# TeensyROM.net
KiCad netlist of a schematic drawn in EAGLE
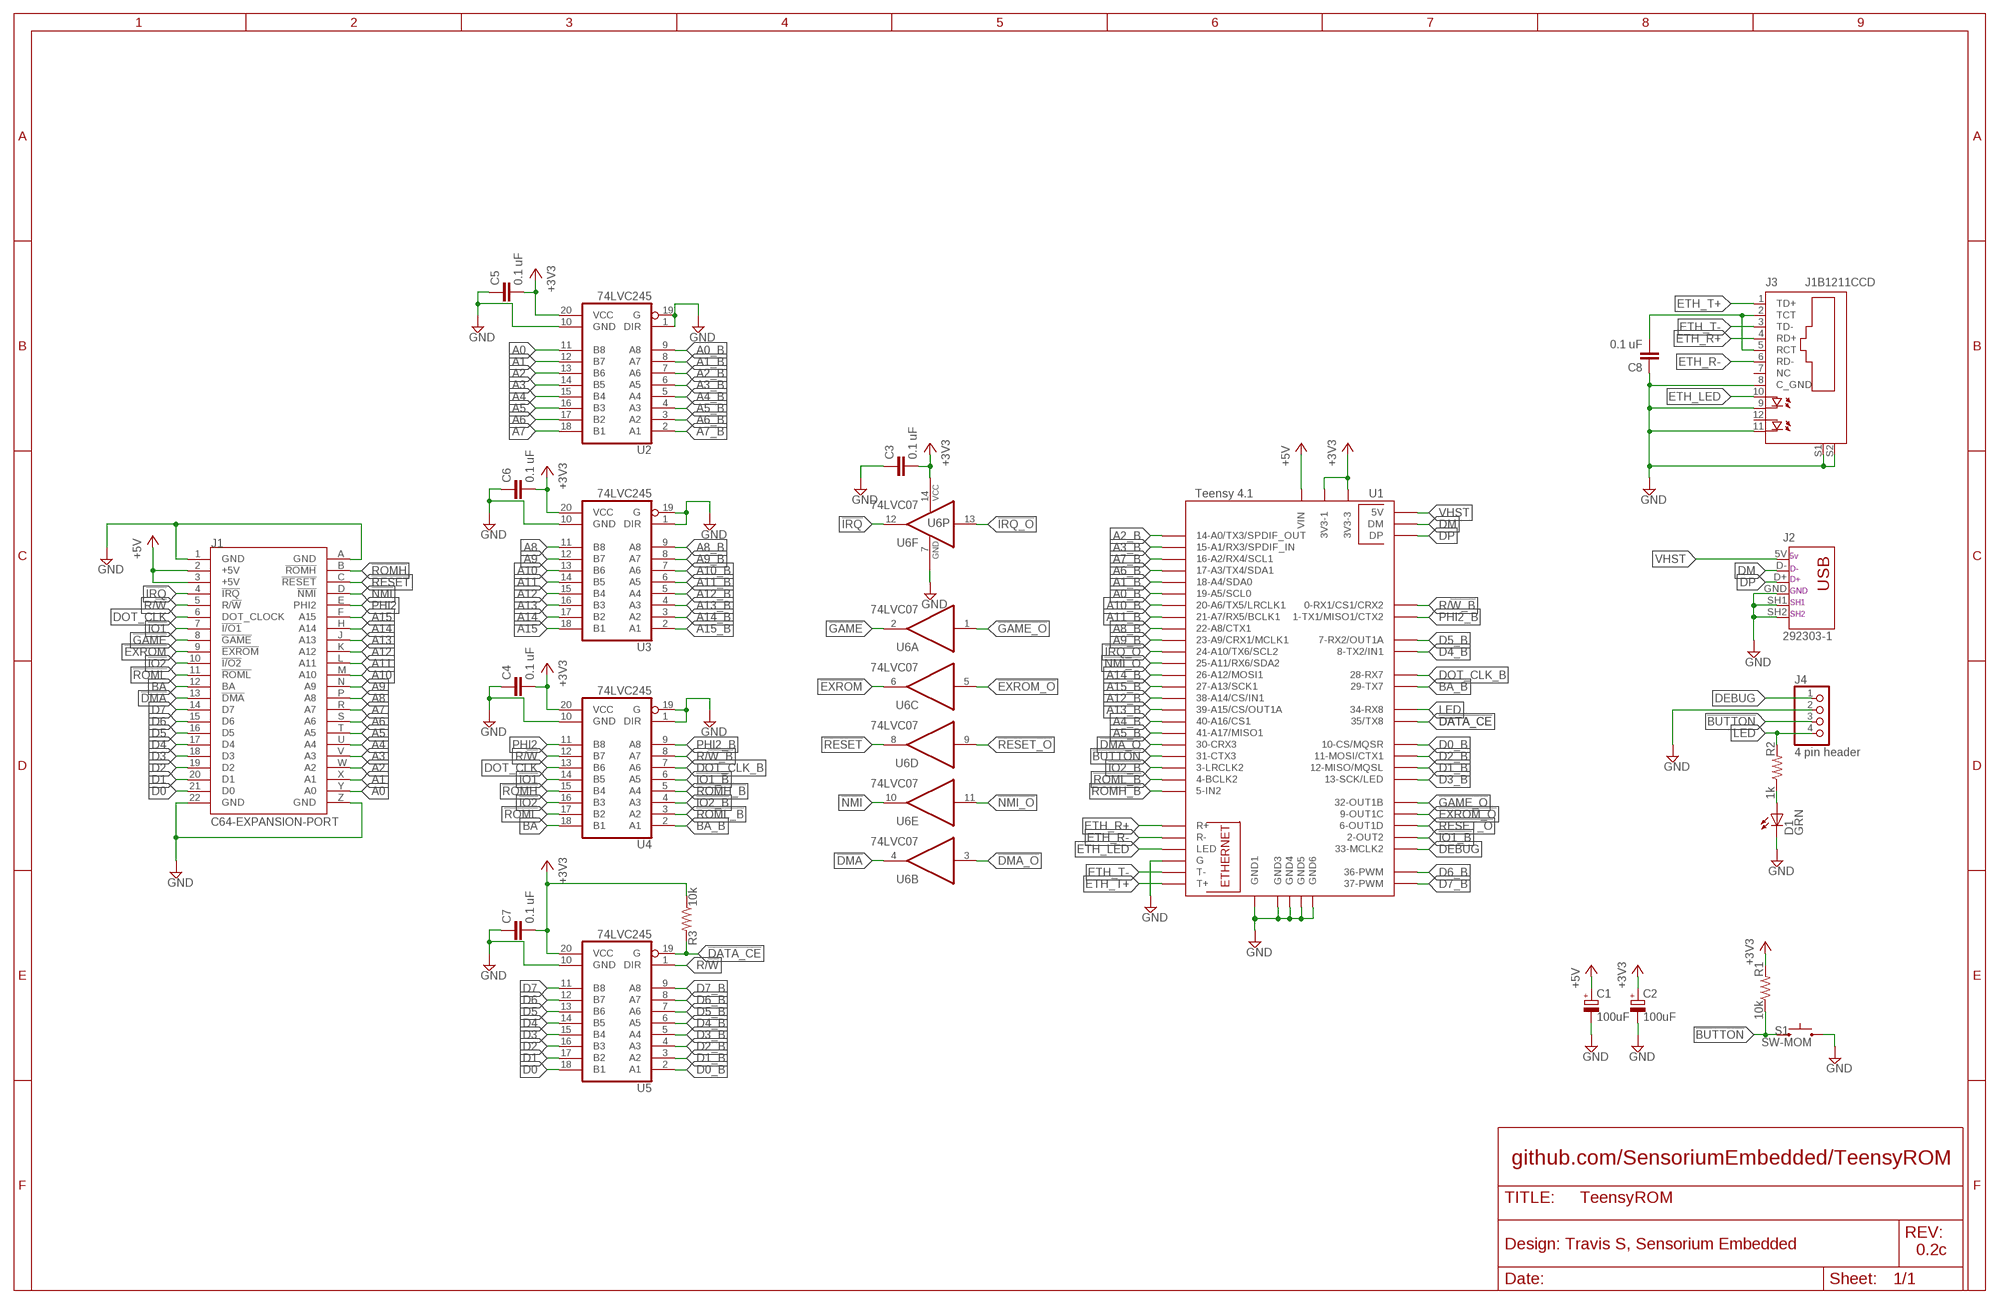
[diagram p0: schematic, sheet 1]

(export (version "E")
  (design (tool "Eeschema 10.0.6"))
  (components
    (comp (ref "C1")
      (value "100uF")
      (footprint "eagle-import:E2-4")
      (libsource (lib "eagle-import") (part "CPOL-EUE2-4"))
    )
    (comp (ref "C2")
      (value "100uF")
      (footprint "eagle-import:E2-4")
      (libsource (lib "eagle-import") (part "CPOL-EUE2-4"))
    )
    (comp (ref "C3")
      (value "0.1 uF")
      (footprint "eagle-import:0805")
      (libsource (lib "eagle-import") (part "CAP-0805-0.1UF-50V"))
    )
    (comp (ref "C4")
      (value "0.1 uF")
      (footprint "eagle-import:0805")
      (libsource (lib "eagle-import") (part "CAP-0805-0.1UF-50V"))
    )
    (comp (ref "C5")
      (value "0.1 uF")
      (footprint "eagle-import:0805")
      (libsource (lib "eagle-import") (part "CAP-0805-0.1UF-50V"))
    )
    (comp (ref "C6")
      (value "0.1 uF")
      (footprint "eagle-import:0805")
      (libsource (lib "eagle-import") (part "CAP-0805-0.1UF-50V"))
    )
    (comp (ref "C7")
      (value "0.1 uF")
      (footprint "eagle-import:0805")
      (libsource (lib "eagle-import") (part "CAP-0805-0.1UF-50V"))
    )
    (comp (ref "C8")
      (value "0.1 uF")
      (footprint "eagle-import:0805")
      (libsource (lib "eagle-import") (part "CAP-0805-0.1UF-50V"))
    )
    (comp (ref "D1")
      (value "GRN")
      (footprint "eagle-import:LED-3MM-PTH")
      (libsource (lib "eagle-import") (part "LED-3MM-GRN"))
    )
    (comp (ref "J1")
      (value "C64-EXPANSION-PORT")
      (footprint "eagle-import:EXPANSIO_SQ")
      (libsource (lib "eagle-import") (part "C64-EXPANSIONPNARROW"))
    )
    (comp (ref "J2")
      (value "292303-1")
      (footprint "eagle-import:USB")
      (libsource (lib "eagle-import") (part "USB-787616"))
    )
    (comp (ref "J3")
      (value "J1B1211CCD")
      (footprint "eagle-import:CONN12_J1B1211CCD_WIZ")
      (fields (field (name "COPYRIGHT") "Copyright (C) 2023 Ultra Librarian. All rights reserved."))
      (libsource (lib "eagle-import") (part "J1B1211CCD"))
    )
    (comp (ref "J4")
      (value "4 pin header")
      (footprint "eagle-import:1X04")
      (libsource (lib "eagle-import") (part "PINHD-1X4"))
    )
    (comp (ref "R1")
      (value "10k")
      (footprint "eagle-import:R0805")
      (libsource (lib "eagle-import") (part "R-US_R0805"))
    )
    (comp (ref "R2")
      (value "1k")
      (footprint "eagle-import:R0805")
      (libsource (lib "eagle-import") (part "R-US_R0805"))
    )
    (comp (ref "R3")
      (value "10k")
      (footprint "eagle-import:R0805")
      (libsource (lib "eagle-import") (part "R-US_R0805"))
    )
    (comp (ref "S1")
      (value "SW-MOM")
      (footprint "eagle-import:TACTILE-PTH")
      (libsource (lib "eagle-import") (part "SWITCH-MOMENTARY-2PTH"))
    )
    (comp (ref "U1")
      (value "Teensy 4.1")
      (footprint "eagle-import:TEENSY41")
      (libsource (lib "eagle-import") (part "TEENSY41"))
    )
    (comp (ref "U2")
      (value "74LVC245")
      (footprint "eagle-import:SO20W")
      (libsource (lib "eagle-import") (part "74245DWLS"))
    )
    (comp (ref "U3")
      (value "74LVC245")
      (footprint "eagle-import:SO20W")
      (libsource (lib "eagle-import") (part "74245DWLS"))
    )
    (comp (ref "U4")
      (value "74LVC245")
      (footprint "eagle-import:SO20W")
      (libsource (lib "eagle-import") (part "74245DWLS"))
    )
    (comp (ref "U5")
      (value "74LVC245")
      (footprint "eagle-import:SO20W")
      (libsource (lib "eagle-import") (part "74245DWLS"))
    )
    (comp (ref "U6")
      (value "74LVC07")
      (footprint "eagle-import:SO14")
      (libsource (lib "eagle-import") (part "7407DLS"))
    )
  )
  (nets
    (net (code "1") (name "+3V3") (class "Default")
      (node (ref "C2") (pin "+") (pinfunction "+_+") (pintype "passive"))
      (node (ref "C3") (pin "2") (pinfunction "2_2") (pintype "passive"))
      (node (ref "C4") (pin "2") (pinfunction "2_2") (pintype "passive"))
      (node (ref "C5") (pin "2") (pinfunction "2_2") (pintype "passive"))
      (node (ref "C6") (pin "2") (pinfunction "2_2") (pintype "passive"))
      (node (ref "C7") (pin "2") (pinfunction "2_2") (pintype "passive"))
      (node (ref "R1") (pin "2") (pinfunction "2_2") (pintype "passive"))
      (node (ref "R3") (pin "1") (pinfunction "1_1") (pintype "passive"))
      (node (ref "U1") (pin "3V3-1") (pinfunction "3V3-1_3V3-1") (pintype "bidirectional"))
      (node (ref "U1") (pin "3V3-3") (pinfunction "3V3-3_3V3-3") (pintype "bidirectional"))
      (node (ref "U2") (pin "20") (pinfunction "VCC_20") (pintype "bidirectional"))
      (node (ref "U3") (pin "20") (pinfunction "VCC_20") (pintype "bidirectional"))
      (node (ref "U4") (pin "20") (pinfunction "VCC_20") (pintype "bidirectional"))
      (node (ref "U5") (pin "20") (pinfunction "VCC_20") (pintype "bidirectional"))
      (node (ref "U6") (pin "14") (pinfunction "VCC_14") (pintype "bidirectional"))
    )
    (net (code "2") (name "+5V") (class "Default")
      (node (ref "C1") (pin "+") (pinfunction "+_+") (pintype "passive"))
      (node (ref "J1") (pin "2") (pinfunction "+5V_2") (pintype "power_in"))
      (node (ref "J1") (pin "3") (pinfunction "+5V_3") (pintype "power_in"))
      (node (ref "U1") (pin "VIN") (pinfunction "VIN_VIN") (pintype "bidirectional"))
    )
    (net (code "3") (name "/R{slash}~{W_B}") (class "Default")
      (node (ref "U1") (pin "0-RX1/CS1/CRX2") (pinfunction "0-RX1/CS1/CRX2_0-RX1/CS1/CRX2") (pintype "bidirectional"))
      (node (ref "U4") (pin "8") (pinfunction "A7_8") (pintype "bidirectional"))
    )
    (net (code "4") (name "/R{slash}~{W}") (class "Default")
      (node (ref "J1") (pin "5") (pinfunction "R/~{W}_5") (pintype "output"))
      (node (ref "U4") (pin "12") (pinfunction "B7_12") (pintype "bidirectional"))
      (node (ref "U5") (pin "1") (pinfunction "DIR_1") (pintype "input"))
    )
    (net (code "5") (name "/~{BUTTON}") (class "Default")
      (node (ref "J4") (pin "3") (pinfunction "3_3") (pintype "passive"))
      (node (ref "R1") (pin "1") (pinfunction "1_1") (pintype "passive"))
      (node (ref "S1") (pin "3") (pinfunction "2_3") (pintype "passive"))
      (node (ref "U1") (pin "31-CTX3") (pinfunction "31-CTX3_31-CTX3") (pintype "bidirectional"))
    )
    (net (code "6") (name "/~{DATA_CE}") (class "Default")
      (node (ref "R3") (pin "2") (pinfunction "2_2") (pintype "passive"))
      (node (ref "U1") (pin "35-TX8") (pinfunction "35/TX8_35-TX8") (pintype "bidirectional"))
      (node (ref "U5") (pin "19") (pinfunction "G_19") (pintype "input"))
    )
    (net (code "7") (name "/~{DMA_O}") (class "Default")
      (node (ref "U1") (pin "30-CRX3") (pinfunction "30-CRX3_30-CRX3") (pintype "bidirectional"))
      (node (ref "U6") (pin "3") (pinfunction "I_3") (pintype "input"))
    )
    (net (code "8") (name "/~{DMA}") (class "Default")
      (node (ref "J1") (pin "13") (pinfunction "~{DMA}_13") (pintype "input"))
      (node (ref "U6") (pin "4") (pinfunction "O_4") (pintype "open_collector"))
    )
    (net (code "9") (name "/~{EXROM_O}") (class "Default")
      (node (ref "U1") (pin "9-OUT1C") (pinfunction "9-OUT1C_9-OUT1C") (pintype "bidirectional"))
      (node (ref "U6") (pin "5") (pinfunction "I_5") (pintype "input"))
    )
    (net (code "10") (name "/~{EXROM}") (class "Default")
      (node (ref "J1") (pin "9") (pinfunction "~{EXROM}_9") (pintype "input"))
      (node (ref "U6") (pin "6") (pinfunction "O_6") (pintype "open_collector"))
    )
    (net (code "11") (name "/~{GAME_O}") (class "Default")
      (node (ref "U1") (pin "32-OUT1B") (pinfunction "32-OUT1B_32-OUT1B") (pintype "bidirectional"))
      (node (ref "U6") (pin "1") (pinfunction "I_1") (pintype "input"))
    )
    (net (code "12") (name "/~{GAME}") (class "Default")
      (node (ref "J1") (pin "8") (pinfunction "~{GAME}_8") (pintype "input"))
      (node (ref "U6") (pin "2") (pinfunction "O_2") (pintype "open_collector"))
    )
    (net (code "13") (name "/~{IO1_B}") (class "Default")
      (node (ref "U1") (pin "2-OUT2") (pinfunction "2-OUT2_2-OUT2") (pintype "bidirectional"))
      (node (ref "U4") (pin "6") (pinfunction "A5_6") (pintype "bidirectional"))
    )
    (net (code "14") (name "/~{IO1}") (class "Default")
      (node (ref "J1") (pin "7") (pinfunction "~{I/O1}_7") (pintype "output"))
      (node (ref "U4") (pin "14") (pinfunction "B5_14") (pintype "bidirectional"))
    )
    (net (code "15") (name "/~{IO2_B}") (class "Default")
      (node (ref "U1") (pin "3-LRCLK2") (pinfunction "3-LRCLK2_3-LRCLK2") (pintype "bidirectional"))
      (node (ref "U4") (pin "4") (pinfunction "A3_4") (pintype "bidirectional"))
    )
    (net (code "16") (name "/~{IO2}") (class "Default")
      (node (ref "J1") (pin "10") (pinfunction "~{I/O2}_10") (pintype "output"))
      (node (ref "U4") (pin "16") (pinfunction "B3_16") (pintype "bidirectional"))
    )
    (net (code "17") (name "/~{IRQ_O}") (class "Default")
      (node (ref "U1") (pin "24-A10/TX6/SCL2") (pinfunction "24-A10/TX6/SCL2_24-A10/TX6/SCL2") (pintype "bidirectional"))
      (node (ref "U6") (pin "13") (pinfunction "I_13") (pintype "input"))
    )
    (net (code "18") (name "/~{IRQ}") (class "Default")
      (node (ref "J1") (pin "4") (pinfunction "~{IRQ}_4") (pintype "input"))
      (node (ref "U6") (pin "12") (pinfunction "O_12") (pintype "open_collector"))
    )
    (net (code "19") (name "/~{NMI_O}") (class "Default")
      (node (ref "U1") (pin "25-A11/RX6/SDA2") (pinfunction "25-A11/RX6/SDA2_25-A11/RX6/SDA2") (pintype "bidirectional"))
      (node (ref "U6") (pin "11") (pinfunction "I_11") (pintype "input"))
    )
    (net (code "20") (name "/~{NMI}") (class "Default")
      (node (ref "J1") (pin "D") (pinfunction "~{NMI}_D") (pintype "input"))
      (node (ref "U6") (pin "10") (pinfunction "O_10") (pintype "open_collector"))
    )
    (net (code "21") (name "/~{RESET_O}") (class "Default")
      (node (ref "U1") (pin "6-OUT1D") (pinfunction "6-OUT1D_6-OUT1D") (pintype "bidirectional"))
      (node (ref "U6") (pin "9") (pinfunction "I_9") (pintype "input"))
    )
    (net (code "22") (name "/~{RESET}") (class "Default")
      (node (ref "J1") (pin "C") (pinfunction "~{RESET}_C") (pintype "open_collector"))
      (node (ref "U6") (pin "8") (pinfunction "O_8") (pintype "open_collector"))
    )
    (net (code "23") (name "/~{ROMH_B}") (class "Default")
      (node (ref "U1") (pin "5-IN2") (pinfunction "5-IN2_5-IN2") (pintype "bidirectional"))
      (node (ref "U4") (pin "5") (pinfunction "A4_5") (pintype "bidirectional"))
    )
    (net (code "24") (name "/~{ROMH}") (class "Default")
      (node (ref "J1") (pin "B") (pinfunction "~{ROMH}_B") (pintype "output"))
      (node (ref "U4") (pin "15") (pinfunction "B4_15") (pintype "bidirectional"))
    )
    (net (code "25") (name "/~{ROML_B}") (class "Default")
      (node (ref "U1") (pin "4-BCLK2") (pinfunction "4-BCLK2_4-BCLK2") (pintype "bidirectional"))
      (node (ref "U4") (pin "3") (pinfunction "A2_3") (pintype "bidirectional"))
    )
    (net (code "26") (name "/~{ROML}") (class "Default")
      (node (ref "J1") (pin "11") (pinfunction "~{ROML}_11") (pintype "output"))
      (node (ref "U4") (pin "17") (pinfunction "B2_17") (pintype "bidirectional"))
    )
    (net (code "27") (name "A0") (class "Default")
      (node (ref "J1") (pin "Y") (pinfunction "A0_Y") (pintype "bidirectional"))
      (node (ref "U2") (pin "11") (pinfunction "B8_11") (pintype "bidirectional"))
    )
    (net (code "28") (name "A0_B") (class "Default")
      (node (ref "U1") (pin "19-A5/SCL0") (pinfunction "19-A5/SCL0_19-A5/SCL0") (pintype "bidirectional"))
      (node (ref "U2") (pin "9") (pinfunction "A8_9") (pintype "bidirectional"))
    )
    (net (code "29") (name "A1") (class "Default")
      (node (ref "J1") (pin "X") (pinfunction "A1_X") (pintype "bidirectional"))
      (node (ref "U2") (pin "12") (pinfunction "B7_12") (pintype "bidirectional"))
    )
    (net (code "30") (name "A1_B") (class "Default")
      (node (ref "U1") (pin "18-A4/SDA0") (pinfunction "18-A4/SDA0_18-A4/SDA0") (pintype "bidirectional"))
      (node (ref "U2") (pin "8") (pinfunction "A7_8") (pintype "bidirectional"))
    )
    (net (code "31") (name "A2") (class "Default")
      (node (ref "J1") (pin "W") (pinfunction "A2_W") (pintype "bidirectional"))
      (node (ref "U2") (pin "13") (pinfunction "B6_13") (pintype "bidirectional"))
    )
    (net (code "32") (name "A2_B") (class "Default")
      (node (ref "U1") (pin "14-A0/TX3/SPDIF_OUT") (pinfunction "14-A0/TX3/SPDIF_OUT_14-A0/TX3/SPDIF_OUT") (pintype "bidirectional"))
      (node (ref "U2") (pin "7") (pinfunction "A6_7") (pintype "bidirectional"))
    )
    (net (code "33") (name "A3") (class "Default")
      (node (ref "J1") (pin "V") (pinfunction "A3_V") (pintype "bidirectional"))
      (node (ref "U2") (pin "14") (pinfunction "B5_14") (pintype "bidirectional"))
    )
    (net (code "34") (name "A3_B") (class "Default")
      (node (ref "U1") (pin "15-A1/RX3/SPDIF_IN") (pinfunction "15-A1/RX3/SPDIF_IN_15-A1/RX3/SPDIF_IN") (pintype "bidirectional"))
      (node (ref "U2") (pin "6") (pinfunction "A5_6") (pintype "bidirectional"))
    )
    (net (code "35") (name "A4") (class "Default")
      (node (ref "J1") (pin "U") (pinfunction "A4_U") (pintype "bidirectional"))
      (node (ref "U2") (pin "15") (pinfunction "B4_15") (pintype "bidirectional"))
    )
    (net (code "36") (name "A4_B") (class "Default")
      (node (ref "U1") (pin "40-A16/CS1") (pinfunction "40-A16/CS1_40-A16/CS1") (pintype "bidirectional"))
      (node (ref "U2") (pin "5") (pinfunction "A4_5") (pintype "bidirectional"))
    )
    (net (code "37") (name "A5") (class "Default")
      (node (ref "J1") (pin "T") (pinfunction "A5_T") (pintype "bidirectional"))
      (node (ref "U2") (pin "16") (pinfunction "B3_16") (pintype "bidirectional"))
    )
    (net (code "38") (name "A5_B") (class "Default")
      (node (ref "U1") (pin "41-A17/MISO1") (pinfunction "41-A17/MISO1_41-A17/MISO1") (pintype "bidirectional"))
      (node (ref "U2") (pin "4") (pinfunction "A3_4") (pintype "bidirectional"))
    )
    (net (code "39") (name "A6") (class "Default")
      (node (ref "J1") (pin "S") (pinfunction "A6_S") (pintype "bidirectional"))
      (node (ref "U2") (pin "17") (pinfunction "B2_17") (pintype "bidirectional"))
    )
    (net (code "40") (name "A6_B") (class "Default")
      (node (ref "U1") (pin "17-A3/TX4/SDA1") (pinfunction "17-A3/TX4/SDA1_17-A3/TX4/SDA1") (pintype "bidirectional"))
      (node (ref "U2") (pin "3") (pinfunction "A2_3") (pintype "bidirectional"))
    )
    (net (code "41") (name "A7") (class "Default")
      (node (ref "J1") (pin "R") (pinfunction "A7_R") (pintype "bidirectional"))
      (node (ref "U2") (pin "18") (pinfunction "B1_18") (pintype "bidirectional"))
    )
    (net (code "42") (name "A7_B") (class "Default")
      (node (ref "U1") (pin "16-A2/RX4/SCL1") (pinfunction "16-A2/RX4/SCL1_16-A2/RX4/SCL1") (pintype "bidirectional"))
      (node (ref "U2") (pin "2") (pinfunction "A1_2") (pintype "bidirectional"))
    )
    (net (code "43") (name "A8") (class "Default")
      (node (ref "J1") (pin "P") (pinfunction "A8_P") (pintype "bidirectional"))
      (node (ref "U3") (pin "11") (pinfunction "B8_11") (pintype "bidirectional"))
    )
    (net (code "44") (name "A8_B") (class "Default")
      (node (ref "U1") (pin "22-A8/CTX1") (pinfunction "22-A8/CTX1_22-A8/CTX1") (pintype "bidirectional"))
      (node (ref "U3") (pin "9") (pinfunction "A8_9") (pintype "bidirectional"))
    )
    (net (code "45") (name "A9") (class "Default")
      (node (ref "J1") (pin "N") (pinfunction "A9_N") (pintype "bidirectional"))
      (node (ref "U3") (pin "12") (pinfunction "B7_12") (pintype "bidirectional"))
    )
    (net (code "46") (name "A9_B") (class "Default")
      (node (ref "U1") (pin "23-A9/CRX1/MCLK1") (pinfunction "23-A9/CRX1/MCLK1_23-A9/CRX1/MCLK1") (pintype "bidirectional"))
      (node (ref "U3") (pin "8") (pinfunction "A7_8") (pintype "bidirectional"))
    )
    (net (code "47") (name "A10") (class "Default")
      (node (ref "J1") (pin "M") (pinfunction "A10_M") (pintype "bidirectional"))
      (node (ref "U3") (pin "13") (pinfunction "B6_13") (pintype "bidirectional"))
    )
    (net (code "48") (name "A10_B") (class "Default")
      (node (ref "U1") (pin "20-A6/TX5/LRCLK1") (pinfunction "20-A6/TX5/LRCLK1_20-A6/TX5/LRCLK1") (pintype "bidirectional"))
      (node (ref "U3") (pin "7") (pinfunction "A6_7") (pintype "bidirectional"))
    )
    (net (code "49") (name "A11") (class "Default")
      (node (ref "J1") (pin "L") (pinfunction "A11_L") (pintype "bidirectional"))
      (node (ref "U3") (pin "14") (pinfunction "B5_14") (pintype "bidirectional"))
    )
    (net (code "50") (name "A11_B") (class "Default")
      (node (ref "U1") (pin "21-A7/RX5/BCLK1") (pinfunction "21-A7/RX5/BCLK1_21-A7/RX5/BCLK1") (pintype "bidirectional"))
      (node (ref "U3") (pin "6") (pinfunction "A5_6") (pintype "bidirectional"))
    )
    (net (code "51") (name "A12") (class "Default")
      (node (ref "J1") (pin "K") (pinfunction "A12_K") (pintype "bidirectional"))
      (node (ref "U3") (pin "15") (pinfunction "B4_15") (pintype "bidirectional"))
    )
    (net (code "52") (name "A12_B") (class "Default")
      (node (ref "U1") (pin "38-A14/CS/IN1") (pinfunction "38-A14/CS/IN1_38-A14/CS/IN1") (pintype "bidirectional"))
      (node (ref "U3") (pin "5") (pinfunction "A4_5") (pintype "bidirectional"))
    )
    (net (code "53") (name "A13") (class "Default")
      (node (ref "J1") (pin "J") (pinfunction "A13_J") (pintype "bidirectional"))
      (node (ref "U3") (pin "16") (pinfunction "B3_16") (pintype "bidirectional"))
    )
    (net (code "54") (name "A13_B") (class "Default")
      (node (ref "U1") (pin "39-A15/CS/OUT1A") (pinfunction "39-A15/CS/OUT1A_39-A15/CS/OUT1A") (pintype "bidirectional"))
      (node (ref "U3") (pin "4") (pinfunction "A3_4") (pintype "bidirectional"))
    )
    (net (code "55") (name "A14") (class "Default")
      (node (ref "J1") (pin "H") (pinfunction "A14_H") (pintype "bidirectional"))
      (node (ref "U3") (pin "17") (pinfunction "B2_17") (pintype "bidirectional"))
    )
    (net (code "56") (name "A14_B") (class "Default")
      (node (ref "U1") (pin "26-A12/MOSI1") (pinfunction "26-A12/MOSI1_26-A12/MOSI1") (pintype "bidirectional"))
      (node (ref "U3") (pin "3") (pinfunction "A2_3") (pintype "bidirectional"))
    )
    (net (code "57") (name "A15") (class "Default")
      (node (ref "J1") (pin "F") (pinfunction "A15_F") (pintype "bidirectional"))
      (node (ref "U3") (pin "18") (pinfunction "B1_18") (pintype "bidirectional"))
    )
    (net (code "58") (name "A15_B") (class "Default")
      (node (ref "U1") (pin "27-A13/SCK1") (pinfunction "27-A13/SCK1_27-A13/SCK1") (pintype "bidirectional"))
      (node (ref "U3") (pin "2") (pinfunction "A1_2") (pintype "bidirectional"))
    )
    (net (code "59") (name "BA") (class "Default")
      (node (ref "J1") (pin "12") (pinfunction "BA_12") (pintype "output"))
      (node (ref "U4") (pin "18") (pinfunction "B1_18") (pintype "bidirectional"))
    )
    (net (code "60") (name "BA_B") (class "Default")
      (node (ref "U1") (pin "29-TX7") (pinfunction "29-TX7_29-TX7") (pintype "bidirectional"))
      (node (ref "U4") (pin "2") (pinfunction "A1_2") (pintype "bidirectional"))
    )
    (net (code "61") (name "D0") (class "Default")
      (node (ref "J1") (pin "21") (pinfunction "D0_21") (pintype "bidirectional"))
      (node (ref "U5") (pin "18") (pinfunction "B1_18") (pintype "bidirectional"))
    )
    (net (code "62") (name "D0_B") (class "Default")
      (node (ref "U1") (pin "10-CS\\MQSR") (pinfunction "10-CS/MQSR_10-CS\\MQSR") (pintype "bidirectional"))
      (node (ref "U5") (pin "2") (pinfunction "A1_2") (pintype "bidirectional"))
    )
    (net (code "63") (name "D1") (class "Default")
      (node (ref "J1") (pin "20") (pinfunction "D1_20") (pintype "bidirectional"))
      (node (ref "U5") (pin "17") (pinfunction "B2_17") (pintype "bidirectional"))
    )
    (net (code "64") (name "D1_B") (class "Default")
      (node (ref "U1") (pin "12-MISO/MQSL") (pinfunction "12-MISO/MQSL_12-MISO/MQSL") (pintype "bidirectional"))
      (node (ref "U5") (pin "3") (pinfunction "A2_3") (pintype "bidirectional"))
    )
    (net (code "65") (name "D2") (class "Default")
      (node (ref "J1") (pin "19") (pinfunction "D2_19") (pintype "bidirectional"))
      (node (ref "U5") (pin "16") (pinfunction "B3_16") (pintype "bidirectional"))
    )
    (net (code "66") (name "D2_B") (class "Default")
      (node (ref "U1") (pin "11-MOSI/CTX1") (pinfunction "11-MOSI/CTX1_11-MOSI/CTX1") (pintype "bidirectional"))
      (node (ref "U5") (pin "4") (pinfunction "A3_4") (pintype "bidirectional"))
    )
    (net (code "67") (name "D3") (class "Default")
      (node (ref "J1") (pin "18") (pinfunction "D3_18") (pintype "bidirectional"))
      (node (ref "U5") (pin "15") (pinfunction "B4_15") (pintype "bidirectional"))
    )
    (net (code "68") (name "D3_B") (class "Default")
      (node (ref "U1") (pin "13-SCK/LED") (pinfunction "13-SCK/LED_13-SCK/LED") (pintype "bidirectional"))
      (node (ref "U5") (pin "5") (pinfunction "A4_5") (pintype "bidirectional"))
    )
    (net (code "69") (name "D4") (class "Default")
      (node (ref "J1") (pin "17") (pinfunction "D4_17") (pintype "bidirectional"))
      (node (ref "U5") (pin "14") (pinfunction "B5_14") (pintype "bidirectional"))
    )
    (net (code "70") (name "D4_B") (class "Default")
      (node (ref "U1") (pin "8-TX2/IN1") (pinfunction "8-TX2/IN1_8-TX2/IN1") (pintype "bidirectional"))
      (node (ref "U5") (pin "6") (pinfunction "A5_6") (pintype "bidirectional"))
    )
    (net (code "71") (name "D5") (class "Default")
      (node (ref "J1") (pin "16") (pinfunction "D5_16") (pintype "bidirectional"))
      (node (ref "U5") (pin "13") (pinfunction "B6_13") (pintype "bidirectional"))
    )
    (net (code "72") (name "D5_B") (class "Default")
      (node (ref "U1") (pin "7-RX2/OUT1A") (pinfunction "7-RX2/OUT1A_7-RX2/OUT1A") (pintype "bidirectional"))
      (node (ref "U5") (pin "7") (pinfunction "A6_7") (pintype "bidirectional"))
    )
    (net (code "73") (name "D6") (class "Default")
      (node (ref "J1") (pin "15") (pinfunction "D6_15") (pintype "bidirectional"))
      (node (ref "U5") (pin "12") (pinfunction "B7_12") (pintype "bidirectional"))
    )
    (net (code "74") (name "D6_B") (class "Default")
      (node (ref "U1") (pin "36-PWM") (pinfunction "36-PWM_36-PWM") (pintype "bidirectional"))
      (node (ref "U5") (pin "8") (pinfunction "A7_8") (pintype "bidirectional"))
    )
    (net (code "75") (name "D7") (class "Default")
      (node (ref "J1") (pin "14") (pinfunction "D7_14") (pintype "bidirectional"))
      (node (ref "U5") (pin "11") (pinfunction "B8_11") (pintype "bidirectional"))
    )
    (net (code "76") (name "D7_B") (class "Default")
      (node (ref "U1") (pin "37-PWM") (pinfunction "37-PWM_37-PWM") (pintype "bidirectional"))
      (node (ref "U5") (pin "9") (pinfunction "A8_9") (pintype "bidirectional"))
    )
    (net (code "77") (name "DEBUG") (class "Default")
      (node (ref "J4") (pin "1") (pinfunction "1_1") (pintype "passive"))
      (node (ref "U1") (pin "33-MCLK2") (pinfunction "33-MCLK2_33-MCLK2") (pintype "bidirectional"))
    )
    (net (code "78") (name "DM") (class "Default")
      (node (ref "J2") (pin "D-") (pinfunction "2_D-") (pintype "passive"))
      (node (ref "U1") (pin "DM") (pinfunction "DM_DM") (pintype "bidirectional"))
    )
    (net (code "79") (name "DOT_CLK") (class "Default")
      (node (ref "J1") (pin "6") (pinfunction "DOT_CLOCK_6") (pintype "output"))
      (node (ref "U4") (pin "13") (pinfunction "B6_13") (pintype "bidirectional"))
    )
    (net (code "80") (name "DOT_CLK_B") (class "Default")
      (node (ref "U1") (pin "28-RX7") (pinfunction "28-RX7_28-RX7") (pintype "bidirectional"))
      (node (ref "U4") (pin "7") (pinfunction "A6_7") (pintype "bidirectional"))
    )
    (net (code "81") (name "DP") (class "Default")
      (node (ref "J2") (pin "D+") (pinfunction "3_D+") (pintype "passive"))
      (node (ref "U1") (pin "DP") (pinfunction "DP_DP") (pintype "bidirectional"))
    )
    (net (code "82") (name "ETH_LED") (class "Default")
      (node (ref "J3") (pin "10") (pinfunction "A_10") (pintype "passive"))
      (node (ref "U1") (pin "LED") (pinfunction "LED_LED") (pintype "bidirectional"))
    )
    (net (code "83") (name "ETH_R+") (class "Default")
      (node (ref "J3") (pin "4") (pinfunction "RD+_4") (pintype "passive"))
      (node (ref "U1") (pin "R+") (pinfunction "R+_R+") (pintype "bidirectional"))
    )
    (net (code "84") (name "ETH_R-") (class "Default")
      (node (ref "J3") (pin "6") (pinfunction "RD-_6") (pintype "passive"))
      (node (ref "U1") (pin "R-") (pinfunction "R-_R-") (pintype "bidirectional"))
    )
    (net (code "85") (name "ETH_T+") (class "Default")
      (node (ref "J3") (pin "1") (pinfunction "TD+_1") (pintype "passive"))
      (node (ref "U1") (pin "T+") (pinfunction "T+_T+") (pintype "bidirectional"))
    )
    (net (code "86") (name "ETH_T-") (class "Default")
      (node (ref "J3") (pin "3") (pinfunction "TD-_3") (pintype "passive"))
      (node (ref "U1") (pin "T-") (pinfunction "T-_T-") (pintype "bidirectional"))
    )
    (net (code "87") (name "GND") (class "Default")
      (node (ref "C1") (pin "-") (pinfunction "-_-") (pintype "passive"))
      (node (ref "C2") (pin "-") (pinfunction "-_-") (pintype "passive"))
      (node (ref "C3") (pin "1") (pinfunction "1_1") (pintype "passive"))
      (node (ref "C4") (pin "1") (pinfunction "1_1") (pintype "passive"))
      (node (ref "C5") (pin "1") (pinfunction "1_1") (pintype "passive"))
      (node (ref "C6") (pin "1") (pinfunction "1_1") (pintype "passive"))
      (node (ref "C7") (pin "1") (pinfunction "1_1") (pintype "passive"))
      (node (ref "C8") (pin "1") (pinfunction "1_1") (pintype "passive"))
      (node (ref "D1") (pin "K") (pinfunction "C_K") (pintype "passive"))
      (node (ref "J1") (pin "1") (pinfunction "GND_1") (pintype "power_in"))
      (node (ref "J1") (pin "22") (pinfunction "GND_22") (pintype "power_in"))
      (node (ref "J1") (pin "A") (pinfunction "GND_A") (pintype "power_in"))
      (node (ref "J1") (pin "Z") (pinfunction "GND_Z") (pintype "power_in"))
      (node (ref "J2") (pin "GND") (pinfunction "4_GND") (pintype "passive"))
      (node (ref "J2") (pin "SH1") (pinfunction "5_SH1") (pintype "passive"))
      (node (ref "J2") (pin "SH2") (pinfunction "6_SH2") (pintype "passive"))
      (node (ref "J3") (pin "11") (pinfunction "C1_11") (pintype "passive"))
      (node (ref "J3") (pin "8") (pinfunction "C_GND_8") (pintype "passive"))
      (node (ref "J3") (pin "9") (pinfunction "C_9") (pintype "passive"))
      (node (ref "J3") (pin "S1") (pinfunction "S1_S1") (pintype "passive"))
      (node (ref "J3") (pin "S2") (pinfunction "S2_S2") (pintype "passive"))
      (node (ref "J4") (pin "2") (pinfunction "2_2") (pintype "passive"))
      (node (ref "S1") (pin "1") (pinfunction "1_1") (pintype "passive"))
      (node (ref "U1") (pin "G") (pinfunction "G_G") (pintype "bidirectional"))
      (node (ref "U1") (pin "GND1") (pinfunction "GND1_GND1") (pintype "bidirectional"))
      (node (ref "U1") (pin "GND3") (pinfunction "GND3_GND3") (pintype "bidirectional"))
      (node (ref "U1") (pin "GND4") (pinfunction "GND4_GND4") (pintype "bidirectional"))
      (node (ref "U1") (pin "GND5") (pinfunction "GND5_GND5") (pintype "bidirectional"))
      (node (ref "U1") (pin "GND6") (pinfunction "GND6_GND6") (pintype "bidirectional"))
      (node (ref "U2") (pin "1") (pinfunction "DIR_1") (pintype "input"))
      (node (ref "U2") (pin "10") (pinfunction "GND_10") (pintype "bidirectional"))
      (node (ref "U2") (pin "19") (pinfunction "G_19") (pintype "input"))
      (node (ref "U3") (pin "1") (pinfunction "DIR_1") (pintype "input"))
      (node (ref "U3") (pin "10") (pinfunction "GND_10") (pintype "bidirectional"))
      (node (ref "U3") (pin "19") (pinfunction "G_19") (pintype "input"))
      (node (ref "U4") (pin "1") (pinfunction "DIR_1") (pintype "input"))
      (node (ref "U4") (pin "10") (pinfunction "GND_10") (pintype "bidirectional"))
      (node (ref "U4") (pin "19") (pinfunction "G_19") (pintype "input"))
      (node (ref "U5") (pin "10") (pinfunction "GND_10") (pintype "bidirectional"))
      (node (ref "U6") (pin "7") (pinfunction "GND_7") (pintype "power_in"))
    )
    (net (code "88") (name "LED") (class "Default")
      (node (ref "J4") (pin "4") (pinfunction "4_4") (pintype "passive"))
      (node (ref "R2") (pin "2") (pinfunction "2_2") (pintype "passive"))
      (node (ref "U1") (pin "34-RX8") (pinfunction "34-RX8_34-RX8") (pintype "bidirectional"))
    )
    (net (code "89") (name "Net-(D1-PadA)") (class "Default")
      (node (ref "D1") (pin "A") (pinfunction "A_A") (pintype "passive"))
      (node (ref "R2") (pin "1") (pinfunction "1_1") (pintype "passive"))
    )
    (net (code "90") (name "Net-(J3-RCT)") (class "Default")
      (node (ref "C8") (pin "2") (pinfunction "2_2") (pintype "passive"))
      (node (ref "J3") (pin "2") (pinfunction "TCT_2") (pintype "passive"))
      (node (ref "J3") (pin "5") (pinfunction "RCT_5") (pintype "passive"))
    )
    (net (code "91") (name "PHI2") (class "Default")
      (node (ref "J1") (pin "E") (pinfunction "PHI2_E") (pintype "output"))
      (node (ref "U4") (pin "11") (pinfunction "B8_11") (pintype "bidirectional"))
    )
    (net (code "92") (name "PHI2_B") (class "Default")
      (node (ref "U1") (pin "1-TX1/MISO1/CTX2") (pinfunction "1-TX1/MISO1/CTX2_1-TX1/MISO1/CTX2") (pintype "bidirectional"))
      (node (ref "U4") (pin "9") (pinfunction "A8_9") (pintype "bidirectional"))
    )
    (net (code "93") (name "VHST") (class "Default")
      (node (ref "J2") (pin "5V") (pinfunction "1_5V") (pintype "passive"))
      (node (ref "U1") (pin "+5V") (pinfunction "5V_+5V") (pintype "bidirectional"))
    )
    (net (code "94") (name "unconnected-(J3-A1-Pad12)") (class "Default")
      (node (ref "J3") (pin "12") (pinfunction "A1_12") (pintype "passive"))
    )
    (net (code "95") (name "unconnected-(J3-NC-Pad7)") (class "Default")
      (node (ref "J3") (pin "7") (pinfunction "NC_7") (pintype "passive"))
    )
  )
)
